# POWER.net
KiCad netlist of a schematic drawn in Altium Designer
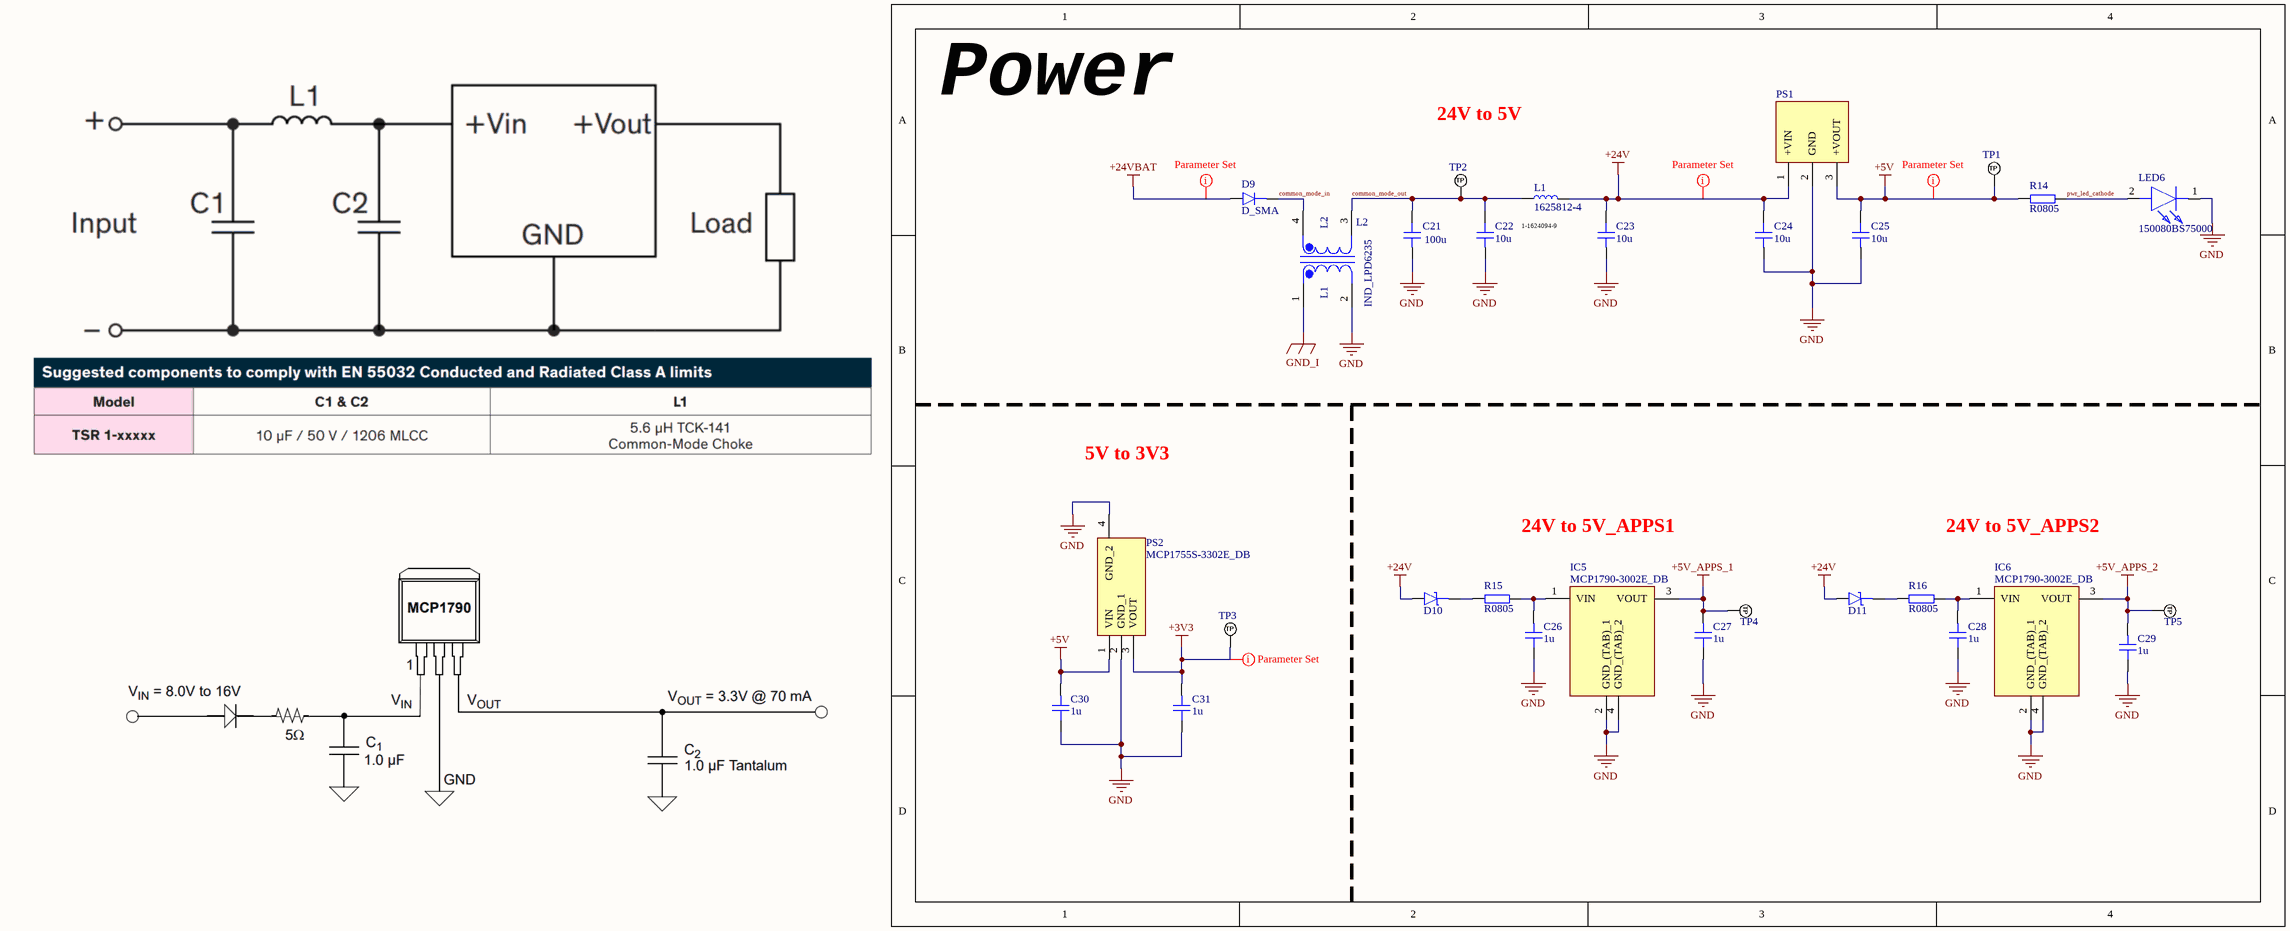
[diagram p0: POWER.SchDoc]

(export (version "E")
  (design (tool "Eeschema 10.0.6"))
  (components
    (comp (ref "C21")
      (value "100u")
      (footprint "CAP_0805")
      (description "Capacitor SMD 0805 10V")
      (libsource (lib "Schematic-Lib-PhilsLab") (part "CAP_0805_10V"))
    )
    (comp (ref "C22")
      (value "10u")
      (footprint "CAP_0805")
      (description "Capacitor SMD 0805 10V")
      (libsource (lib "Schematic-Lib-PhilsLab") (part "CAP_0805_10V"))
    )
    (comp (ref "C23")
      (value "10u")
      (footprint "CAP_0805")
      (description "Capacitor SMD 0805 10V")
      (libsource (lib "Schematic-Lib-PhilsLab") (part "CAP_0805_10V"))
    )
    (comp (ref "C24")
      (value "10u")
      (footprint "CAP_0805")
      (description "Capacitor SMD 0805 10V")
      (libsource (lib "Schematic-Lib-PhilsLab") (part "CAP_0805_10V"))
    )
    (comp (ref "C25")
      (value "10u")
      (footprint "CAP_0805")
      (description "Capacitor SMD 0805 10V")
      (libsource (lib "Schematic-Lib-PhilsLab") (part "CAP_0805_10V"))
    )
    (comp (ref "C26")
      (value "1u")
      (footprint "CAP_0805")
      (description "Capacitor SMD 0805 10V")
      (libsource (lib "Schematic-Lib-PhilsLab") (part "CAP_0805_10V"))
    )
    (comp (ref "C27")
      (value "1u")
      (footprint "CAP_0805")
      (description "Capacitor SMD 0805 10V")
      (libsource (lib "Schematic-Lib-PhilsLab") (part "CAP_0805_10V"))
    )
    (comp (ref "C28")
      (value "1u")
      (footprint "CAP_0805")
      (description "Capacitor SMD 0805 10V")
      (libsource (lib "Schematic-Lib-PhilsLab") (part "CAP_0805_10V"))
    )
    (comp (ref "C29")
      (value "1u")
      (footprint "CAP_0805")
      (description "Capacitor SMD 0805 10V")
      (libsource (lib "Schematic-Lib-PhilsLab") (part "CAP_0805_10V"))
    )
    (comp (ref "C30")
      (value "1u")
      (footprint "CAP_0805")
      (description "Capacitor SMD 0805 10V")
      (libsource (lib "Schematic-Lib-PhilsLab") (part "CAP_0805_10V"))
    )
    (comp (ref "C31")
      (value "1u")
      (footprint "CAP_0805")
      (description "Capacitor SMD 0805 10V")
      (libsource (lib "Schematic-Lib-PhilsLab") (part "CAP_0805_10V"))
    )
    (comp (ref "D9")
      (value "D_SMA")
      (footprint "DO-214AC-2 (SMA)")
      (description "Diode SMD SMA (DO-214AA)")
      (libsource (lib "Schematic-Lib-PhilsLab") (part "D_SMA"))
    )
    (comp (ref "D10")
      (value "D_SCHOTTKY_SOD_323")
      (footprint "SOD-323")
      (description "Diode Schottky SMD SOD-323")
      (libsource (lib "PhilsLab") (part "D_SCHOTTKY_SOD_323"))
    )
    (comp (ref "D11")
      (value "D_SCHOTTKY_SOD_323")
      (footprint "SOD-323")
      (description "Diode Schottky SMD SOD-323")
      (libsource (lib "PhilsLab") (part "D_SCHOTTKY_SOD_323"))
    )
    (comp (ref "IC5")
      (value "MCP1790-3002E_DB")
      (footprint "Pedro_pcb_lib:SOT230P700X180-4N")
      (description "Integrated Circuit")
      (fields
        (field (name "MANUFACTURER_PART_NUMBER") "MCP1790-3002E/DB")
        (field (name "MOUSER PART NUMBER") "579-MCP1790-3002E/DB")
      )
      (libsource (lib "*") (part "MCP1790-3002E_DB"))
    )
    (comp (ref "IC6")
      (value "MCP1790-3002E_DB")
      (footprint "Pedro_pcb_lib:SOT230P700X180-4N")
      (description "Integrated Circuit")
      (fields
        (field (name "MANUFACTURER_PART_NUMBER") "MCP1790-3002E/DB")
        (field (name "MOUSER PART NUMBER") "579-MCP1790-3002E/DB")
      )
      (libsource (lib "*") (part "MCP1790-3002E_DB"))
    )
    (comp (ref "L1")
      (value "1625812-4")
      (footprint "147873-2 smd button")
      (description "TE 1625812-4")
      (libsource (lib "Pedro_Integrated_Library") (part "Power_Inductor"))
    )
    (comp (ref "L2")
      (value "IND_LPD6235")
      (footprint "IND_LPD6235")
      (libsource (lib "Pedro_Integrated_Library") (part "IND_LPD6235"))
    )
    (comp (ref "LED6")
      (value "150080BS75000")
      (footprint "LEDC2012X80N")
      (description "LED")
      (fields (field (name "MOUSER PART NUMBER") "710-150080BS75000"))
      (libsource (lib "Pedro_Integrated_Library") (part "150080BS75000"))
    )
    (comp (ref "PS1")
      (value "R-78E5.0-0.5")
      (footprint "R78E5005")
      (description "Power Supply")
      (fields (field (name "MOUSER PART NUMBER") "919-R-78E5.0-0.5"))
      (libsource (lib "Pedro_Integrated_Library") (part "R-78E5.0-0.5"))
    )
    (comp (ref "PS2")
      (value "MCP1755S-3302E_DB")
      (footprint "Pedro_pcb_lib:SOT230P700X180-4N")
      (description "Power Supply")
      (fields
        (field (name "MANUFACTURER_PART_NUMBER") "MCP1755S-3302E/DB")
        (field (name "MOUSER PART NUMBER") "579-MCP1755S-3302EDB")
      )
      (libsource (lib "*") (part "MCP1755S-3302E_DB"))
    )
    (comp (ref "R14")
      (value "R0805")
      (footprint "RES_0805")
      (description "Resistor SMD 0805")
      (libsource (lib "Schematic-Lib-PhilsLab") (part "RES_0805"))
    )
    (comp (ref "R15")
      (value "R0805")
      (footprint "RES_0805")
      (description "Resistor SMD 0805")
      (libsource (lib "Schematic-Lib-PhilsLab") (part "RES_0805"))
    )
    (comp (ref "R16")
      (value "R0805")
      (footprint "RES_0805")
      (description "Resistor SMD 0805")
      (libsource (lib "Schematic-Lib-PhilsLab") (part "RES_0805"))
    )
    (comp (ref "TP1")
      (value "TP_NOBOM")
      (footprint "PAD_RND_1MM")
      (description "Test Point Round 1mm (NO BOM)")
      (libsource (lib "Schematic-Lib-PhilsLab") (part "TEST_POINT_RND_1MM"))
    )
    (comp (ref "TP2")
      (value "TP_NOBOM")
      (footprint "PAD_RND_1MM")
      (description "Test Point Round 1mm (NO BOM)")
      (libsource (lib "Schematic-Lib-PhilsLab") (part "TEST_POINT_RND_1MM"))
    )
    (comp (ref "TP3")
      (value "TP_NOBOM")
      (footprint "PAD_RND_1MM")
      (description "Test Point Round 1mm (NO BOM)")
      (libsource (lib "Schematic-Lib-PhilsLab") (part "TEST_POINT_RND_1MM"))
    )
    (comp (ref "TP4")
      (value "TP_NOBOM")
      (footprint "PAD_RND_1MM")
      (description "Test Point Round 1mm (NO BOM)")
      (libsource (lib "Schematic-Lib-PhilsLab") (part "TEST_POINT_RND_1MM"))
    )
    (comp (ref "TP5")
      (value "TP_NOBOM")
      (footprint "PAD_RND_1MM")
      (description "Test Point Round 1mm (NO BOM)")
      (libsource (lib "Schematic-Lib-PhilsLab") (part "TEST_POINT_RND_1MM"))
    )
  )
  (nets
    (net (code "1") (name "+3V3") (class "Default")
      (node (ref "C31") (pin "1") (pinfunction "1_1") (pintype "passive"))
      (node (ref "PS2") (pin "3") (pinfunction "VOUT_3") (pintype "passive"))
      (node (ref "TP3") (pin "1") (pinfunction "TP_1") (pintype "passive"))
    )
    (net (code "2") (name "+5V") (class "Default")
      (node (ref "C25") (pin "2") (pinfunction "2_2") (pintype "passive"))
      (node (ref "C30") (pin "1") (pinfunction "1_1") (pintype "passive"))
      (node (ref "PS1") (pin "3") (pinfunction "+VOUT_3") (pintype "passive"))
      (node (ref "PS2") (pin "1") (pinfunction "VIN_1") (pintype "passive"))
      (node (ref "R14") (pin "1") (pinfunction "1_1") (pintype "passive"))
      (node (ref "TP1") (pin "1") (pinfunction "TP_1") (pintype "passive"))
    )
    (net (code "3") (name "+5V_APPS_1") (class "Default")
      (node (ref "C27") (pin "1") (pinfunction "1_1") (pintype "passive"))
      (node (ref "IC5") (pin "3") (pinfunction "VOUT_3") (pintype "passive"))
      (node (ref "TP4") (pin "1") (pinfunction "TP_1") (pintype "passive"))
    )
    (net (code "4") (name "+5V_APPS_2") (class "Default")
      (node (ref "C29") (pin "1") (pinfunction "1_1") (pintype "passive"))
      (node (ref "IC6") (pin "3") (pinfunction "VOUT_3") (pintype "passive"))
      (node (ref "TP5") (pin "1") (pinfunction "TP_1") (pintype "passive"))
    )
    (net (code "5") (name "+24V") (class "Default")
      (node (ref "C23") (pin "2") (pinfunction "2_2") (pintype "passive"))
      (node (ref "C24") (pin "2") (pinfunction "2_2") (pintype "passive"))
      (node (ref "D10") (pin "A") (pinfunction "A_A") (pintype "passive"))
      (node (ref "D11") (pin "A") (pinfunction "A_A") (pintype "passive"))
      (node (ref "L1") (pin "2") (pinfunction "2_2") (pintype "passive"))
      (node (ref "PS1") (pin "1") (pinfunction "+VIN_1") (pintype "passive"))
    )
    (net (code "6") (name "+24VBAT") (class "Default")
      (node (ref "D9") (pin "A") (pinfunction "A_A") (pintype "passive"))
    )
    (net (code "7") (name "/common_mode_in") (class "Default")
      (node (ref "D9") (pin "K") (pinfunction "K_K") (pintype "passive"))
      (node (ref "L2") (pin "4") (pinfunction "4_4") (pintype "passive"))
    )
    (net (code "8") (name "/common_mode_out") (class "Default")
      (node (ref "C21") (pin "2") (pinfunction "2_2") (pintype "passive"))
      (node (ref "C22") (pin "2") (pinfunction "2_2") (pintype "passive"))
      (node (ref "L1") (pin "1") (pinfunction "1_1") (pintype "passive"))
      (node (ref "L2") (pin "3") (pinfunction "3_3") (pintype "passive"))
      (node (ref "TP2") (pin "1") (pinfunction "TP_1") (pintype "passive"))
    )
    (net (code "9") (name "/pwr_led_cathode") (class "Default")
      (node (ref "LED6") (pin "2") (pinfunction "A_2") (pintype "passive"))
      (node (ref "R14") (pin "2") (pinfunction "2_2") (pintype "passive"))
    )
    (net (code "10") (name "GND") (class "Default")
      (node (ref "C21") (pin "1") (pinfunction "1_1") (pintype "passive"))
      (node (ref "C22") (pin "1") (pinfunction "1_1") (pintype "passive"))
      (node (ref "C23") (pin "1") (pinfunction "1_1") (pintype "passive"))
      (node (ref "C24") (pin "1") (pinfunction "1_1") (pintype "passive"))
      (node (ref "C25") (pin "1") (pinfunction "1_1") (pintype "passive"))
      (node (ref "C26") (pin "2") (pinfunction "2_2") (pintype "passive"))
      (node (ref "C27") (pin "2") (pinfunction "2_2") (pintype "passive"))
      (node (ref "C28") (pin "2") (pinfunction "2_2") (pintype "passive"))
      (node (ref "C29") (pin "2") (pinfunction "2_2") (pintype "passive"))
      (node (ref "C30") (pin "2") (pinfunction "2_2") (pintype "passive"))
      (node (ref "C31") (pin "2") (pinfunction "2_2") (pintype "passive"))
      (node (ref "IC5") (pin "2") (pinfunction "GND_(TAB)_1_2") (pintype "passive"))
      (node (ref "IC5") (pin "4") (pinfunction "GND_(TAB)_2_4") (pintype "passive"))
      (node (ref "IC6") (pin "2") (pinfunction "GND_(TAB)_1_2") (pintype "passive"))
      (node (ref "IC6") (pin "4") (pinfunction "GND_(TAB)_2_4") (pintype "passive"))
      (node (ref "L2") (pin "2") (pinfunction "2_2") (pintype "passive"))
      (node (ref "LED6") (pin "1") (pinfunction "K_1") (pintype "passive"))
      (node (ref "PS1") (pin "2") (pinfunction "GND_2") (pintype "passive"))
      (node (ref "PS2") (pin "2") (pinfunction "GND_1_2") (pintype "passive"))
      (node (ref "PS2") (pin "4") (pinfunction "GND_2_4") (pintype "passive"))
    )
    (net (code "11") (name "GND_I") (class "Default")
      (node (ref "L2") (pin "1") (pinfunction "1_1") (pintype "passive"))
    )
    (net (code "12") (name "Net-(D10-PadK)") (class "Default")
      (node (ref "D10") (pin "K") (pinfunction "K_K") (pintype "passive"))
      (node (ref "R15") (pin "2") (pinfunction "2_2") (pintype "passive"))
    )
    (net (code "13") (name "Net-(D11-PadK)") (class "Default")
      (node (ref "D11") (pin "K") (pinfunction "K_K") (pintype "passive"))
      (node (ref "R16") (pin "2") (pinfunction "2_2") (pintype "passive"))
    )
    (net (code "14") (name "Net-(IC5-VIN)") (class "Default")
      (node (ref "C26") (pin "1") (pinfunction "1_1") (pintype "passive"))
      (node (ref "IC5") (pin "1") (pinfunction "VIN_1") (pintype "passive"))
      (node (ref "R15") (pin "1") (pinfunction "1_1") (pintype "passive"))
    )
    (net (code "15") (name "Net-(IC6-VIN)") (class "Default")
      (node (ref "C28") (pin "1") (pinfunction "1_1") (pintype "passive"))
      (node (ref "IC6") (pin "1") (pinfunction "VIN_1") (pintype "passive"))
      (node (ref "R16") (pin "1") (pinfunction "1_1") (pintype "passive"))
    )
  )
)
